# 14_Zynq_Power.net
KiCad netlist of a schematic drawn in Altium Designer
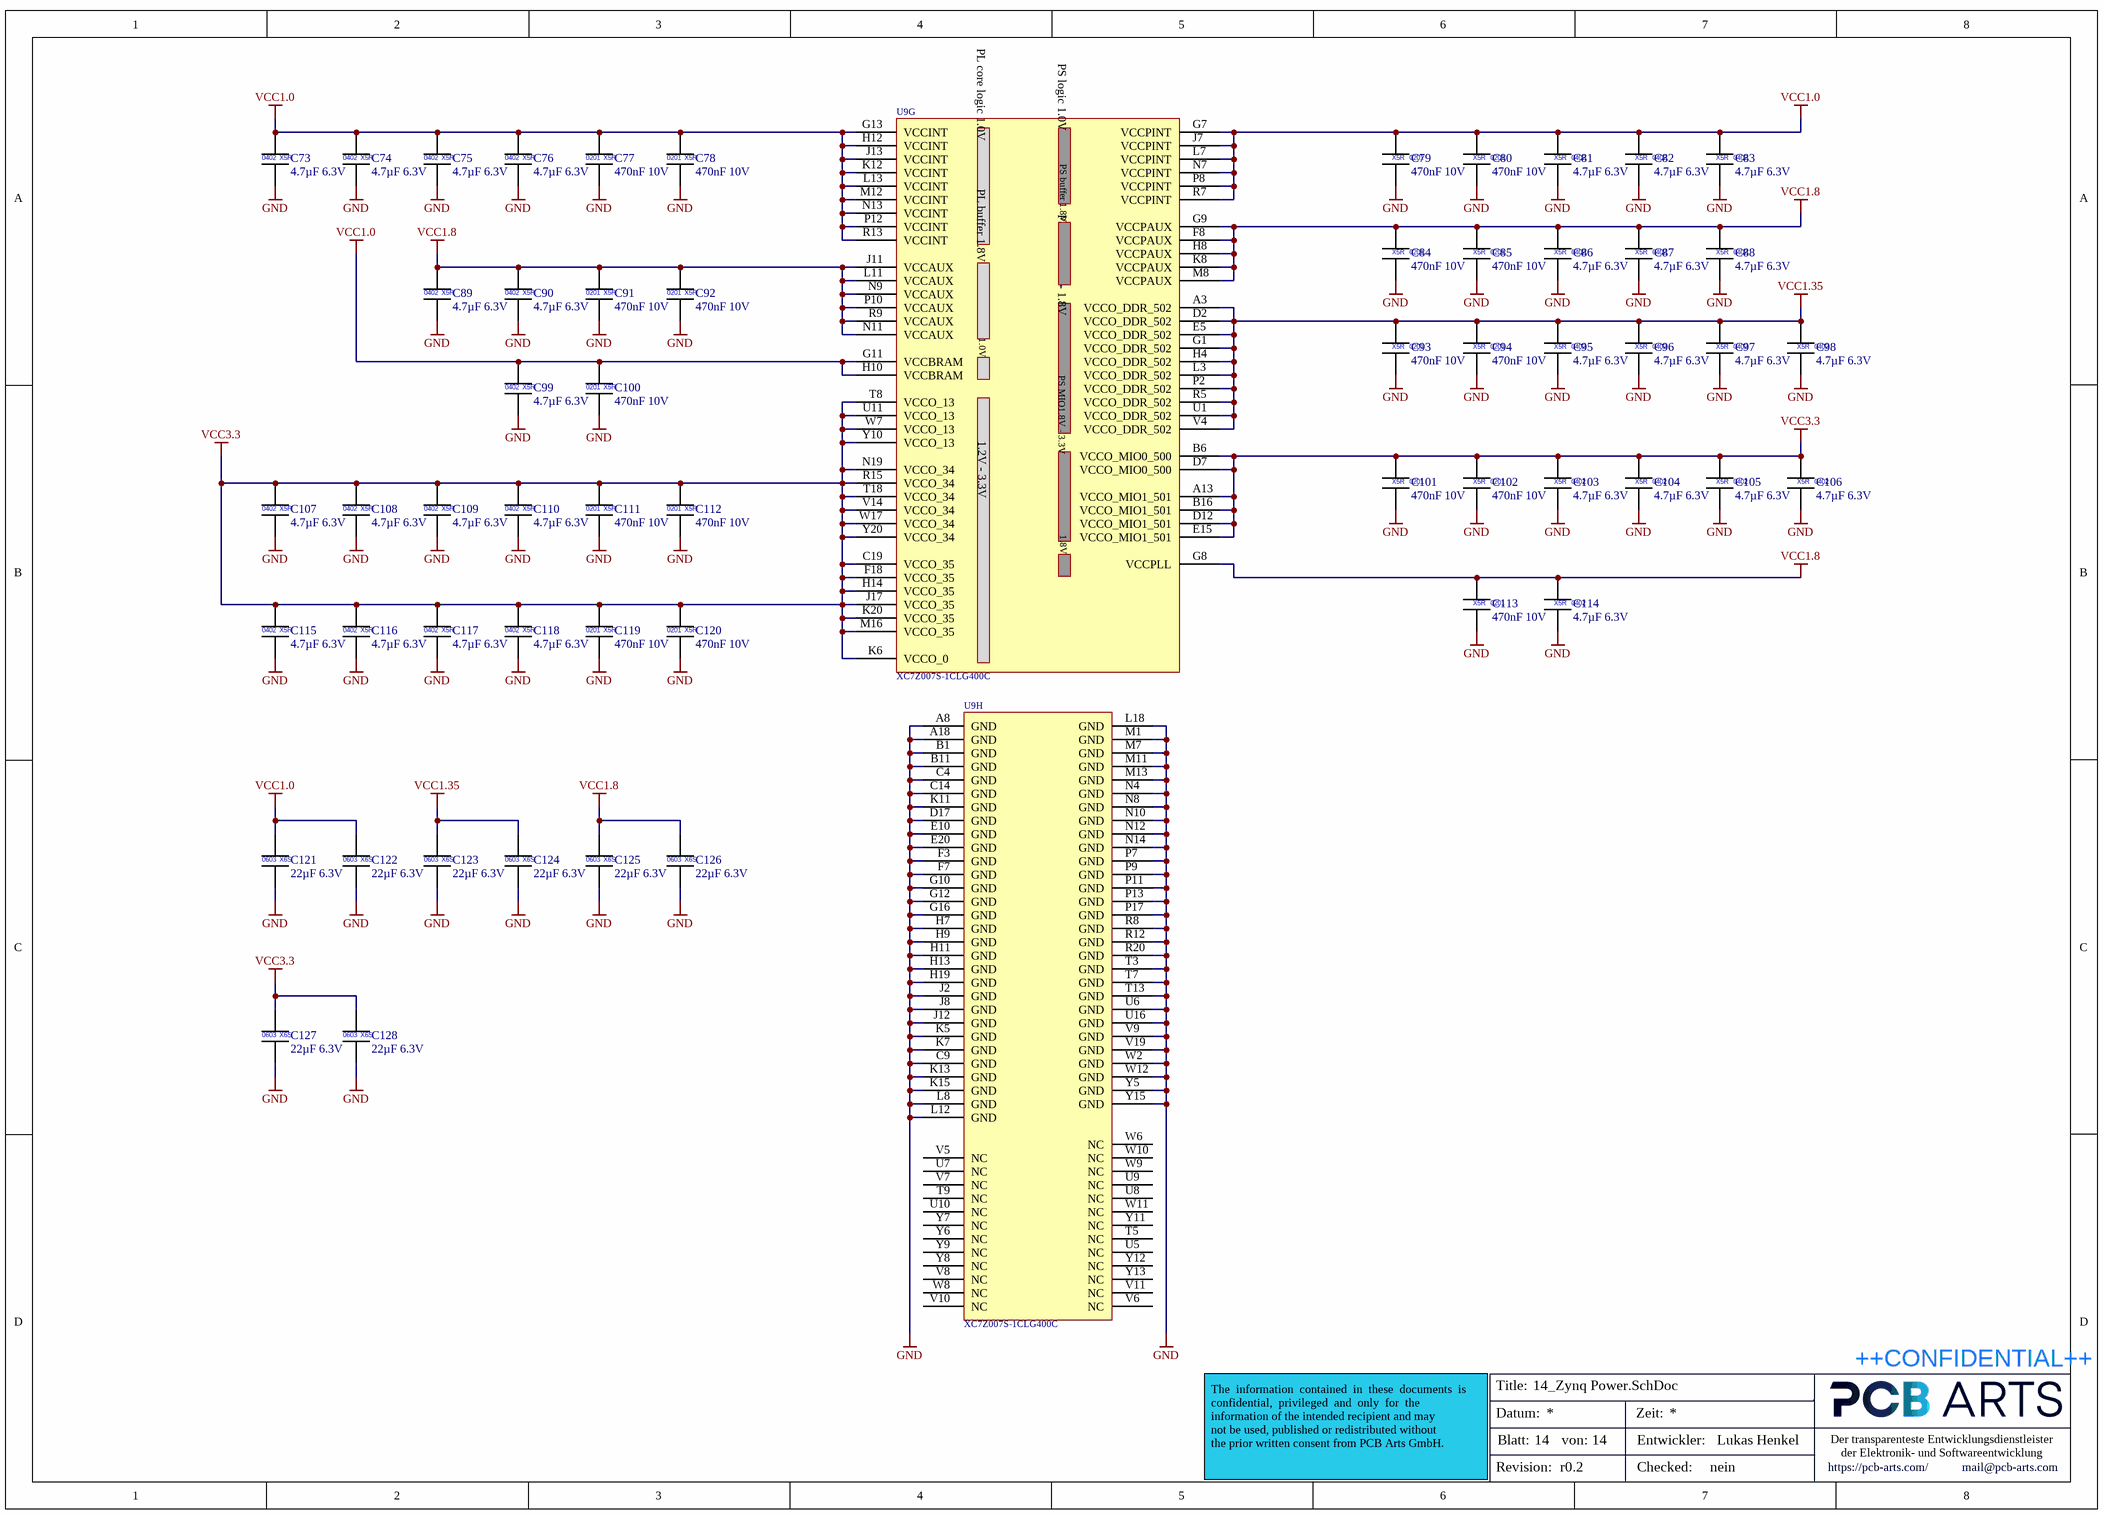
[diagram p0: 14_Zynq Power.SchDoc]

(export (version "E")
  (design (tool "Eeschema 10.0.6"))
  (components
    (comp (ref "C73")
      (value "4.7µF 6.3V")
      (footprint "Zynq-Feather-HD:CAPC1005X06L")
      (description "Multilayer Ceramic Capacitors MLCC - SMD/SMT 0402 6.3VDC")
      (libsource (lib "Zynq-Feather-HD") (part "CAP_0402_4.7µ_6.3V"))
    )
    (comp (ref "C74")
      (value "4.7µF 6.3V")
      (footprint "Zynq-Feather-HD:CAPC1005X06L")
      (description "Multilayer Ceramic Capacitors MLCC - SMD/SMT 0402 6.3VDC")
      (libsource (lib "Zynq-Feather-HD") (part "CAP_0402_4.7µ_6.3V"))
    )
    (comp (ref "C75")
      (value "4.7µF 6.3V")
      (footprint "Zynq-Feather-HD:CAPC1005X06L")
      (description "Multilayer Ceramic Capacitors MLCC - SMD/SMT 0402 6.3VDC")
      (libsource (lib "Zynq-Feather-HD") (part "CAP_0402_4.7µ_6.3V"))
    )
    (comp (ref "C76")
      (value "4.7µF 6.3V")
      (footprint "Zynq-Feather-HD:CAPC1005X06L")
      (description "Multilayer Ceramic Capacitors MLCC - SMD/SMT 0402 6.3VDC")
      (libsource (lib "Zynq-Feather-HD") (part "CAP_0402_4.7µ_6.3V"))
    )
    (comp (ref "C77")
      (value "470nF 10V")
      (footprint "Zynq-Feather-HD:CAPC0603X03L")
      (description "Multilayer Ceramic Capacitors MLCC - SMD/SMT 0201 10VDC")
      (libsource (lib "Zynq-Feather-HD") (part "CAP_0201_470nF_10V"))
    )
    (comp (ref "C78")
      (value "470nF 10V")
      (footprint "Zynq-Feather-HD:CAPC0603X03L")
      (description "Multilayer Ceramic Capacitors MLCC - SMD/SMT 0201 10VDC")
      (libsource (lib "Zynq-Feather-HD") (part "CAP_0201_470nF_10V"))
    )
    (comp (ref "C79")
      (value "470nF 10V")
      (footprint "Zynq-Feather-HD:CAPC0603X03L")
      (description "Multilayer Ceramic Capacitors MLCC - SMD/SMT 0201 10VDC")
      (libsource (lib "Zynq-Feather-HD") (part "CAP_0201_470nF_10V"))
    )
    (comp (ref "C80")
      (value "470nF 10V")
      (footprint "Zynq-Feather-HD:CAPC0603X03L")
      (description "Multilayer Ceramic Capacitors MLCC - SMD/SMT 0201 10VDC")
      (libsource (lib "Zynq-Feather-HD") (part "CAP_0201_470nF_10V"))
    )
    (comp (ref "C81")
      (value "4.7µF 6.3V")
      (footprint "Zynq-Feather-HD:CAPC1005X06L")
      (description "Multilayer Ceramic Capacitors MLCC - SMD/SMT 0402 6.3VDC")
      (libsource (lib "Zynq-Feather-HD") (part "CAP_0402_4.7µ_6.3V"))
    )
    (comp (ref "C82")
      (value "4.7µF 6.3V")
      (footprint "Zynq-Feather-HD:CAPC1005X06L")
      (description "Multilayer Ceramic Capacitors MLCC - SMD/SMT 0402 6.3VDC")
      (libsource (lib "Zynq-Feather-HD") (part "CAP_0402_4.7µ_6.3V"))
    )
    (comp (ref "C83")
      (value "4.7µF 6.3V")
      (footprint "Zynq-Feather-HD:CAPC1005X06L")
      (description "Multilayer Ceramic Capacitors MLCC - SMD/SMT 0402 6.3VDC")
      (libsource (lib "Zynq-Feather-HD") (part "CAP_0402_4.7µ_6.3V"))
    )
    (comp (ref "C84")
      (value "470nF 10V")
      (footprint "Zynq-Feather-HD:CAPC0603X03L")
      (description "Multilayer Ceramic Capacitors MLCC - SMD/SMT 0201 10VDC")
      (libsource (lib "Zynq-Feather-HD") (part "CAP_0201_470nF_10V"))
    )
    (comp (ref "C85")
      (value "470nF 10V")
      (footprint "Zynq-Feather-HD:CAPC0603X03L")
      (description "Multilayer Ceramic Capacitors MLCC - SMD/SMT 0201 10VDC")
      (libsource (lib "Zynq-Feather-HD") (part "CAP_0201_470nF_10V"))
    )
    (comp (ref "C86")
      (value "4.7µF 6.3V")
      (footprint "Zynq-Feather-HD:CAPC1005X06L")
      (description "Multilayer Ceramic Capacitors MLCC - SMD/SMT 0402 6.3VDC")
      (libsource (lib "Zynq-Feather-HD") (part "CAP_0402_4.7µ_6.3V"))
    )
    (comp (ref "C87")
      (value "4.7µF 6.3V")
      (footprint "Zynq-Feather-HD:CAPC1005X06L")
      (description "Multilayer Ceramic Capacitors MLCC - SMD/SMT 0402 6.3VDC")
      (libsource (lib "Zynq-Feather-HD") (part "CAP_0402_4.7µ_6.3V"))
    )
    (comp (ref "C88")
      (value "4.7µF 6.3V")
      (footprint "Zynq-Feather-HD:CAPC1005X06L")
      (description "Multilayer Ceramic Capacitors MLCC - SMD/SMT 0402 6.3VDC")
      (libsource (lib "Zynq-Feather-HD") (part "CAP_0402_4.7µ_6.3V"))
    )
    (comp (ref "C89")
      (value "4.7µF 6.3V")
      (footprint "Zynq-Feather-HD:CAPC1005X06L")
      (description "Multilayer Ceramic Capacitors MLCC - SMD/SMT 0402 6.3VDC")
      (libsource (lib "Zynq-Feather-HD") (part "CAP_0402_4.7µ_6.3V"))
    )
    (comp (ref "C90")
      (value "4.7µF 6.3V")
      (footprint "Zynq-Feather-HD:CAPC1005X06L")
      (description "Multilayer Ceramic Capacitors MLCC - SMD/SMT 0402 6.3VDC")
      (libsource (lib "Zynq-Feather-HD") (part "CAP_0402_4.7µ_6.3V"))
    )
    (comp (ref "C91")
      (value "470nF 10V")
      (footprint "Zynq-Feather-HD:CAPC0603X03L")
      (description "Multilayer Ceramic Capacitors MLCC - SMD/SMT 0201 10VDC")
      (libsource (lib "Zynq-Feather-HD") (part "CAP_0201_470nF_10V"))
    )
    (comp (ref "C92")
      (value "470nF 10V")
      (footprint "Zynq-Feather-HD:CAPC0603X03L")
      (description "Multilayer Ceramic Capacitors MLCC - SMD/SMT 0201 10VDC")
      (libsource (lib "Zynq-Feather-HD") (part "CAP_0201_470nF_10V"))
    )
    (comp (ref "C93")
      (value "470nF 10V")
      (footprint "Zynq-Feather-HD:CAPC0603X03L")
      (description "Multilayer Ceramic Capacitors MLCC - SMD/SMT 0201 10VDC")
      (libsource (lib "Zynq-Feather-HD") (part "CAP_0201_470nF_10V"))
    )
    (comp (ref "C94")
      (value "470nF 10V")
      (footprint "Zynq-Feather-HD:CAPC0603X03L")
      (description "Multilayer Ceramic Capacitors MLCC - SMD/SMT 0201 10VDC")
      (libsource (lib "Zynq-Feather-HD") (part "CAP_0201_470nF_10V"))
    )
    (comp (ref "C95")
      (value "4.7µF 6.3V")
      (footprint "Zynq-Feather-HD:CAPC1005X06L")
      (description "Multilayer Ceramic Capacitors MLCC - SMD/SMT 0402 6.3VDC")
      (libsource (lib "Zynq-Feather-HD") (part "CAP_0402_4.7µ_6.3V"))
    )
    (comp (ref "C96")
      (value "4.7µF 6.3V")
      (footprint "Zynq-Feather-HD:CAPC1005X06L")
      (description "Multilayer Ceramic Capacitors MLCC - SMD/SMT 0402 6.3VDC")
      (libsource (lib "Zynq-Feather-HD") (part "CAP_0402_4.7µ_6.3V"))
    )
    (comp (ref "C97")
      (value "4.7µF 6.3V")
      (footprint "Zynq-Feather-HD:CAPC1005X06L")
      (description "Multilayer Ceramic Capacitors MLCC - SMD/SMT 0402 6.3VDC")
      (libsource (lib "Zynq-Feather-HD") (part "CAP_0402_4.7µ_6.3V"))
    )
    (comp (ref "C98")
      (value "4.7µF 6.3V")
      (footprint "Zynq-Feather-HD:CAPC1005X06L")
      (description "Multilayer Ceramic Capacitors MLCC - SMD/SMT 0402 6.3VDC")
      (libsource (lib "Zynq-Feather-HD") (part "CAP_0402_4.7µ_6.3V"))
    )
    (comp (ref "C99")
      (value "4.7µF 6.3V")
      (footprint "Zynq-Feather-HD:CAPC1005X06L")
      (description "Multilayer Ceramic Capacitors MLCC - SMD/SMT 0402 6.3VDC")
      (libsource (lib "Zynq-Feather-HD") (part "CAP_0402_4.7µ_6.3V"))
    )
    (comp (ref "C100")
      (value "470nF 10V")
      (footprint "Zynq-Feather-HD:CAPC0603X03L")
      (description "Multilayer Ceramic Capacitors MLCC - SMD/SMT 0201 10VDC")
      (libsource (lib "Zynq-Feather-HD") (part "CAP_0201_470nF_10V"))
    )
    (comp (ref "C101")
      (value "470nF 10V")
      (footprint "Zynq-Feather-HD:CAPC0603X03L")
      (description "Multilayer Ceramic Capacitors MLCC - SMD/SMT 0201 10VDC")
      (libsource (lib "Zynq-Feather-HD") (part "CAP_0201_470nF_10V"))
    )
    (comp (ref "C102")
      (value "470nF 10V")
      (footprint "Zynq-Feather-HD:CAPC0603X03L")
      (description "Multilayer Ceramic Capacitors MLCC - SMD/SMT 0201 10VDC")
      (libsource (lib "Zynq-Feather-HD") (part "CAP_0201_470nF_10V"))
    )
    (comp (ref "C103")
      (value "4.7µF 6.3V")
      (footprint "Zynq-Feather-HD:CAPC1005X06L")
      (description "Multilayer Ceramic Capacitors MLCC - SMD/SMT 0402 6.3VDC")
      (libsource (lib "Zynq-Feather-HD") (part "CAP_0402_4.7µ_6.3V"))
    )
    (comp (ref "C104")
      (value "4.7µF 6.3V")
      (footprint "Zynq-Feather-HD:CAPC1005X06L")
      (description "Multilayer Ceramic Capacitors MLCC - SMD/SMT 0402 6.3VDC")
      (libsource (lib "Zynq-Feather-HD") (part "CAP_0402_4.7µ_6.3V"))
    )
    (comp (ref "C105")
      (value "4.7µF 6.3V")
      (footprint "Zynq-Feather-HD:CAPC1005X06L")
      (description "Multilayer Ceramic Capacitors MLCC - SMD/SMT 0402 6.3VDC")
      (libsource (lib "Zynq-Feather-HD") (part "CAP_0402_4.7µ_6.3V"))
    )
    (comp (ref "C106")
      (value "4.7µF 6.3V")
      (footprint "Zynq-Feather-HD:CAPC1005X06L")
      (description "Multilayer Ceramic Capacitors MLCC - SMD/SMT 0402 6.3VDC")
      (libsource (lib "Zynq-Feather-HD") (part "CAP_0402_4.7µ_6.3V"))
    )
    (comp (ref "C107")
      (value "4.7µF 6.3V")
      (footprint "Zynq-Feather-HD:CAPC1005X06L")
      (description "Multilayer Ceramic Capacitors MLCC - SMD/SMT 0402 6.3VDC")
      (libsource (lib "Zynq-Feather-HD") (part "CAP_0402_4.7µ_6.3V"))
    )
    (comp (ref "C108")
      (value "4.7µF 6.3V")
      (footprint "Zynq-Feather-HD:CAPC1005X06L")
      (description "Multilayer Ceramic Capacitors MLCC - SMD/SMT 0402 6.3VDC")
      (libsource (lib "Zynq-Feather-HD") (part "CAP_0402_4.7µ_6.3V"))
    )
    (comp (ref "C109")
      (value "4.7µF 6.3V")
      (footprint "Zynq-Feather-HD:CAPC1005X06L")
      (description "Multilayer Ceramic Capacitors MLCC - SMD/SMT 0402 6.3VDC")
      (libsource (lib "Zynq-Feather-HD") (part "CAP_0402_4.7µ_6.3V"))
    )
    (comp (ref "C110")
      (value "4.7µF 6.3V")
      (footprint "Zynq-Feather-HD:CAPC1005X06L")
      (description "Multilayer Ceramic Capacitors MLCC - SMD/SMT 0402 6.3VDC")
      (libsource (lib "Zynq-Feather-HD") (part "CAP_0402_4.7µ_6.3V"))
    )
    (comp (ref "C111")
      (value "470nF 10V")
      (footprint "Zynq-Feather-HD:CAPC0603X03L")
      (description "Multilayer Ceramic Capacitors MLCC - SMD/SMT 0201 10VDC")
      (libsource (lib "Zynq-Feather-HD") (part "CAP_0201_470nF_10V"))
    )
    (comp (ref "C112")
      (value "470nF 10V")
      (footprint "Zynq-Feather-HD:CAPC0603X03L")
      (description "Multilayer Ceramic Capacitors MLCC - SMD/SMT 0201 10VDC")
      (libsource (lib "Zynq-Feather-HD") (part "CAP_0201_470nF_10V"))
    )
    (comp (ref "C113")
      (value "470nF 10V")
      (footprint "Zynq-Feather-HD:CAPC0603X03L")
      (description "Multilayer Ceramic Capacitors MLCC - SMD/SMT 0201 10VDC")
      (libsource (lib "Zynq-Feather-HD") (part "CAP_0201_470nF_10V"))
    )
    (comp (ref "C114")
      (value "4.7µF 6.3V")
      (footprint "Zynq-Feather-HD:CAPC1005X06L")
      (description "Multilayer Ceramic Capacitors MLCC - SMD/SMT 0402 6.3VDC")
      (libsource (lib "Zynq-Feather-HD") (part "CAP_0402_4.7µ_6.3V"))
    )
    (comp (ref "C115")
      (value "4.7µF 6.3V")
      (footprint "Zynq-Feather-HD:CAPC1005X06L")
      (description "Multilayer Ceramic Capacitors MLCC - SMD/SMT 0402 6.3VDC")
      (libsource (lib "Zynq-Feather-HD") (part "CAP_0402_4.7µ_6.3V"))
    )
    (comp (ref "C116")
      (value "4.7µF 6.3V")
      (footprint "Zynq-Feather-HD:CAPC1005X06L")
      (description "Multilayer Ceramic Capacitors MLCC - SMD/SMT 0402 6.3VDC")
      (libsource (lib "Zynq-Feather-HD") (part "CAP_0402_4.7µ_6.3V"))
    )
    (comp (ref "C117")
      (value "4.7µF 6.3V")
      (footprint "Zynq-Feather-HD:CAPC1005X06L")
      (description "Multilayer Ceramic Capacitors MLCC - SMD/SMT 0402 6.3VDC")
      (libsource (lib "Zynq-Feather-HD") (part "CAP_0402_4.7µ_6.3V"))
    )
    (comp (ref "C118")
      (value "4.7µF 6.3V")
      (footprint "Zynq-Feather-HD:CAPC1005X06L")
      (description "Multilayer Ceramic Capacitors MLCC - SMD/SMT 0402 6.3VDC")
      (libsource (lib "Zynq-Feather-HD") (part "CAP_0402_4.7µ_6.3V"))
    )
    (comp (ref "C119")
      (value "470nF 10V")
      (footprint "Zynq-Feather-HD:CAPC0603X03L")
      (description "Multilayer Ceramic Capacitors MLCC - SMD/SMT 0201 10VDC")
      (libsource (lib "Zynq-Feather-HD") (part "CAP_0201_470nF_10V"))
    )
    (comp (ref "C120")
      (value "470nF 10V")
      (footprint "Zynq-Feather-HD:CAPC0603X03L")
      (description "Multilayer Ceramic Capacitors MLCC - SMD/SMT 0201 10VDC")
      (libsource (lib "Zynq-Feather-HD") (part "CAP_0201_470nF_10V"))
    )
    (comp (ref "C121")
      (value "22µF 6.3V")
      (footprint "Zynq-Feather-HD:CAPC1608X10L")
      (description "Multilayer Ceramic Capacitors MLCC - SMD/SMT 0603 6.3VDC")
      (libsource (lib "Zynq-Feather-HD") (part "CAP_0603_22µ_6.3V"))
    )
    (comp (ref "C122")
      (value "22µF 6.3V")
      (footprint "Zynq-Feather-HD:CAPC1608X10L")
      (description "Multilayer Ceramic Capacitors MLCC - SMD/SMT 0603 6.3VDC")
      (libsource (lib "Zynq-Feather-HD") (part "CAP_0603_22µ_6.3V"))
    )
    (comp (ref "C123")
      (value "22µF 6.3V")
      (footprint "Zynq-Feather-HD:CAPC1608X10L")
      (description "Multilayer Ceramic Capacitors MLCC - SMD/SMT 0603 6.3VDC")
      (libsource (lib "Zynq-Feather-HD") (part "CAP_0603_22µ_6.3V"))
    )
    (comp (ref "C124")
      (value "22µF 6.3V")
      (footprint "Zynq-Feather-HD:CAPC1608X10L")
      (description "Multilayer Ceramic Capacitors MLCC - SMD/SMT 0603 6.3VDC")
      (libsource (lib "Zynq-Feather-HD") (part "CAP_0603_22µ_6.3V"))
    )
    (comp (ref "C125")
      (value "22µF 6.3V")
      (footprint "Zynq-Feather-HD:CAPC1608X10L")
      (description "Multilayer Ceramic Capacitors MLCC - SMD/SMT 0603 6.3VDC")
      (libsource (lib "Zynq-Feather-HD") (part "CAP_0603_22µ_6.3V"))
    )
    (comp (ref "C126")
      (value "22µF 6.3V")
      (footprint "Zynq-Feather-HD:CAPC1608X10L")
      (description "Multilayer Ceramic Capacitors MLCC - SMD/SMT 0603 6.3VDC")
      (libsource (lib "Zynq-Feather-HD") (part "CAP_0603_22µ_6.3V"))
    )
    (comp (ref "C127")
      (value "22µF 6.3V")
      (footprint "Zynq-Feather-HD:CAPC1608X10L")
      (description "Multilayer Ceramic Capacitors MLCC - SMD/SMT 0603 6.3VDC")
      (libsource (lib "Zynq-Feather-HD") (part "CAP_0603_22µ_6.3V"))
    )
    (comp (ref "C128")
      (value "22µF 6.3V")
      (footprint "Zynq-Feather-HD:CAPC1608X10L")
      (description "Multilayer Ceramic Capacitors MLCC - SMD/SMT 0603 6.3VDC")
      (libsource (lib "Zynq-Feather-HD") (part "CAP_0603_22µ_6.3V"))
    )
    (comp (ref "U9")
      (value "XC7Z007S-1CLG400C")
      (footprint "Zynq-Feather-HD:BGA400C80P20X20_1700X1700X160")
      (description "XC7Z007S-1CLG400C_Processors - Application Specialised")
      (libsource (lib "Zynq-Feather-HD") (part "XC7Z007S-1CLG400C_Processors - Application Specialised"))
    )
  )
  (nets
    (net (code "1") (name "GND") (class "Default")
      (node (ref "C100") (pin "2") (pinfunction "2_2") (pintype "passive"))
      (node (ref "C101") (pin "2") (pinfunction "2_2") (pintype "passive"))
      (node (ref "C102") (pin "2") (pinfunction "2_2") (pintype "passive"))
      (node (ref "C103") (pin "2") (pinfunction "2_2") (pintype "passive"))
      (node (ref "C104") (pin "2") (pinfunction "2_2") (pintype "passive"))
      (node (ref "C105") (pin "2") (pinfunction "2_2") (pintype "passive"))
      (node (ref "C106") (pin "2") (pinfunction "2_2") (pintype "passive"))
      (node (ref "C107") (pin "2") (pinfunction "2_2") (pintype "passive"))
      (node (ref "C108") (pin "2") (pinfunction "2_2") (pintype "passive"))
      (node (ref "C109") (pin "2") (pinfunction "2_2") (pintype "passive"))
      (node (ref "C110") (pin "2") (pinfunction "2_2") (pintype "passive"))
      (node (ref "C111") (pin "2") (pinfunction "2_2") (pintype "passive"))
      (node (ref "C112") (pin "2") (pinfunction "2_2") (pintype "passive"))
      (node (ref "C113") (pin "2") (pinfunction "2_2") (pintype "passive"))
      (node (ref "C114") (pin "2") (pinfunction "2_2") (pintype "passive"))
      (node (ref "C115") (pin "2") (pinfunction "2_2") (pintype "passive"))
      (node (ref "C116") (pin "2") (pinfunction "2_2") (pintype "passive"))
      (node (ref "C117") (pin "2") (pinfunction "2_2") (pintype "passive"))
      (node (ref "C118") (pin "2") (pinfunction "2_2") (pintype "passive"))
      (node (ref "C119") (pin "2") (pinfunction "2_2") (pintype "passive"))
      (node (ref "C120") (pin "2") (pinfunction "2_2") (pintype "passive"))
      (node (ref "C121") (pin "2") (pinfunction "2_2") (pintype "passive"))
      (node (ref "C122") (pin "2") (pinfunction "2_2") (pintype "passive"))
      (node (ref "C123") (pin "2") (pinfunction "2_2") (pintype "passive"))
      (node (ref "C124") (pin "2") (pinfunction "2_2") (pintype "passive"))
      (node (ref "C125") (pin "2") (pinfunction "2_2") (pintype "passive"))
      (node (ref "C126") (pin "2") (pinfunction "2_2") (pintype "passive"))
      (node (ref "C127") (pin "2") (pinfunction "2_2") (pintype "passive"))
      (node (ref "C128") (pin "2") (pinfunction "2_2") (pintype "passive"))
      (node (ref "C73") (pin "2") (pinfunction "2_2") (pintype "passive"))
      (node (ref "C74") (pin "2") (pinfunction "2_2") (pintype "passive"))
      (node (ref "C75") (pin "2") (pinfunction "2_2") (pintype "passive"))
      (node (ref "C76") (pin "2") (pinfunction "2_2") (pintype "passive"))
      (node (ref "C77") (pin "2") (pinfunction "2_2") (pintype "passive"))
      (node (ref "C78") (pin "2") (pinfunction "2_2") (pintype "passive"))
      (node (ref "C79") (pin "2") (pinfunction "2_2") (pintype "passive"))
      (node (ref "C80") (pin "2") (pinfunction "2_2") (pintype "passive"))
      (node (ref "C81") (pin "2") (pinfunction "2_2") (pintype "passive"))
      (node (ref "C82") (pin "2") (pinfunction "2_2") (pintype "passive"))
      (node (ref "C83") (pin "2") (pinfunction "2_2") (pintype "passive"))
      (node (ref "C84") (pin "2") (pinfunction "2_2") (pintype "passive"))
      (node (ref "C85") (pin "2") (pinfunction "2_2") (pintype "passive"))
      (node (ref "C86") (pin "2") (pinfunction "2_2") (pintype "passive"))
      (node (ref "C87") (pin "2") (pinfunction "2_2") (pintype "passive"))
      (node (ref "C88") (pin "2") (pinfunction "2_2") (pintype "passive"))
      (node (ref "C89") (pin "2") (pinfunction "2_2") (pintype "passive"))
      (node (ref "C90") (pin "2") (pinfunction "2_2") (pintype "passive"))
      (node (ref "C91") (pin "2") (pinfunction "2_2") (pintype "passive"))
      (node (ref "C92") (pin "2") (pinfunction "2_2") (pintype "passive"))
      (node (ref "C93") (pin "2") (pinfunction "2_2") (pintype "passive"))
      (node (ref "C94") (pin "2") (pinfunction "2_2") (pintype "passive"))
      (node (ref "C95") (pin "2") (pinfunction "2_2") (pintype "passive"))
      (node (ref "C96") (pin "2") (pinfunction "2_2") (pintype "passive"))
      (node (ref "C97") (pin "2") (pinfunction "2_2") (pintype "passive"))
      (node (ref "C98") (pin "2") (pinfunction "2_2") (pintype "passive"))
      (node (ref "C99") (pin "2") (pinfunction "2_2") (pintype "passive"))
      (node (ref "U9") (pin "A18") (pinfunction "GND_A18") (pintype "passive"))
      (node (ref "U9") (pin "A8") (pinfunction "GND_A8") (pintype "passive"))
      (node (ref "U9") (pin "B1") (pinfunction "GND_B1") (pintype "passive"))
      (node (ref "U9") (pin "B11") (pinfunction "GND_B11") (pintype "passive"))
      (node (ref "U9") (pin "C14") (pinfunction "GND_C14") (pintype "passive"))
      (node (ref "U9") (pin "C4") (pinfunction "GND_C4") (pintype "passive"))
      (node (ref "U9") (pin "C9") (pinfunction "GND_C9") (pintype "passive"))
      (node (ref "U9") (pin "D17") (pinfunction "GND_D17") (pintype "passive"))
      (node (ref "U9") (pin "E10") (pinfunction "GND_E10") (pintype "passive"))
      (node (ref "U9") (pin "E20") (pinfunction "GND_E20") (pintype "passive"))
      (node (ref "U9") (pin "F3") (pinfunction "GND_F3") (pintype "passive"))
      (node (ref "U9") (pin "F7") (pinfunction "GND_F7") (pintype "passive"))
      (node (ref "U9") (pin "G10") (pinfunction "GND_G10") (pintype "passive"))
      (node (ref "U9") (pin "G12") (pinfunction "GND_G12") (pintype "passive"))
      (node (ref "U9") (pin "G16") (pinfunction "GND_G16") (pintype "passive"))
      (node (ref "U9") (pin "H11") (pinfunction "GND_H11") (pintype "passive"))
      (node (ref "U9") (pin "H13") (pinfunction "GND_H13") (pintype "passive"))
      (node (ref "U9") (pin "H19") (pinfunction "GND_H19") (pintype "passive"))
      (node (ref "U9") (pin "H7") (pinfunction "GND_H7") (pintype "passive"))
      (node (ref "U9") (pin "H9") (pinfunction "GND_H9") (pintype "passive"))
      (node (ref "U9") (pin "J12") (pinfunction "GND_J12") (pintype "passive"))
      (node (ref "U9") (pin "J2") (pinfunction "GND_J2") (pintype "passive"))
      (node (ref "U9") (pin "J8") (pinfunction "GND_J8") (pintype "passive"))
      (node (ref "U9") (pin "K11") (pinfunction "GND_K11") (pintype "passive"))
      (node (ref "U9") (pin "K13") (pinfunction "GND_K13") (pintype "passive"))
      (node (ref "U9") (pin "K15") (pinfunction "GND_K15") (pintype "passive"))
      (node (ref "U9") (pin "K5") (pinfunction "GND_K5") (pintype "passive"))
      (node (ref "U9") (pin "K7") (pinfunction "GND_K7") (pintype "passive"))
      (node (ref "U9") (pin "L12") (pinfunction "GND_L12") (pintype "passive"))
      (node (ref "U9") (pin "L18") (pinfunction "GND_L18") (pintype "passive"))
      (node (ref "U9") (pin "L8") (pinfunction "GND_L8") (pintype "passive"))
      (node (ref "U9") (pin "M1") (pinfunction "GND_M1") (pintype "passive"))
      (node (ref "U9") (pin "M11") (pinfunction "GND_M11") (pintype "passive"))
      (node (ref "U9") (pin "M13") (pinfunction "GND_M13") (pintype "passive"))
      (node (ref "U9") (pin "M7") (pinfunction "GND_M7") (pintype "passive"))
      (node (ref "U9") (pin "N10") (pinfunction "GND_N10") (pintype "passive"))
      (node (ref "U9") (pin "N12") (pinfunction "GND_N12") (pintype "passive"))
      (node (ref "U9") (pin "N14") (pinfunction "GND_N14") (pintype "passive"))
      (node (ref "U9") (pin "N4") (pinfunction "GND_N4") (pintype "passive"))
      (node (ref "U9") (pin "N8") (pinfunction "GND_N8") (pintype "passive"))
      (node (ref "U9") (pin "P11") (pinfunction "GND_P11") (pintype "passive"))
      (node (ref "U9") (pin "P13") (pinfunction "GND_P13") (pintype "passive"))
      (node (ref "U9") (pin "P17") (pinfunction "GND_P17") (pintype "passive"))
      (node (ref "U9") (pin "P7") (pinfunction "GND_P7") (pintype "passive"))
      (node (ref "U9") (pin "P9") (pinfunction "GND_P9") (pintype "passive"))
      (node (ref "U9") (pin "R12") (pinfunction "GND_R12") (pintype "passive"))
      (node (ref "U9") (pin "R20") (pinfunction "GND_R20") (pintype "passive"))
      (node (ref "U9") (pin "R8") (pinfunction "GND_R8") (pintype "passive"))
      (node (ref "U9") (pin "T13") (pinfunction "GND_T13") (pintype "passive"))
      (node (ref "U9") (pin "T3") (pinfunction "GND_T3") (pintype "passive"))
      (node (ref "U9") (pin "T7") (pinfunction "GND_T7") (pintype "passive"))
      (node (ref "U9") (pin "U16") (pinfunction "GND_U16") (pintype "passive"))
      (node (ref "U9") (pin "U6") (pinfunction "GND_U6") (pintype "passive"))
      (node (ref "U9") (pin "V19") (pinfunction "GND_V19") (pintype "passive"))
      (node (ref "U9") (pin "V9") (pinfunction "GND_V9") (pintype "passive"))
      (node (ref "U9") (pin "W12") (pinfunction "GND_W12") (pintype "passive"))
      (node (ref "U9") (pin "W2") (pinfunction "GND_W2") (pintype "passive"))
      (node (ref "U9") (pin "Y15") (pinfunction "GND_Y15") (pintype "passive"))
      (node (ref "U9") (pin "Y5") (pinfunction "GND_Y5") (pintype "passive"))
    )
    (net (code "2") (name "VCC1.0") (class "Default")
      (node (ref "C100") (pin "1") (pinfunction "1_1") (pintype "passive"))
      (node (ref "C121") (pin "1") (pinfunction "1_1") (pintype "passive"))
      (node (ref "C122") (pin "1") (pinfunction "1_1") (pintype "passive"))
      (node (ref "C73") (pin "1") (pinfunction "1_1") (pintype "passive"))
      (node (ref "C74") (pin "1") (pinfunction "1_1") (pintype "passive"))
      (node (ref "C75") (pin "1") (pinfunction "1_1") (pintype "passive"))
      (node (ref "C76") (pin "1") (pinfunction "1_1") (pintype "passive"))
      (node (ref "C77") (pin "1") (pinfunction "1_1") (pintype "passive"))
      (node (ref "C78") (pin "1") (pinfunction "1_1") (pintype "passive"))
      (node (ref "C79") (pin "1") (pinfunction "1_1") (pintype "passive"))
      (node (ref "C80") (pin "1") (pinfunction "1_1") (pintype "passive"))
      (node (ref "C81") (pin "1") (pinfunction "1_1") (pintype "passive"))
      (node (ref "C82") (pin "1") (pinfunction "1_1") (pintype "passive"))
      (node (ref "C83") (pin "1") (pinfunction "1_1") (pintype "passive"))
      (node (ref "C99") (pin "1") (pinfunction "1_1") (pintype "passive"))
      (node (ref "U9") (pin "G11") (pinfunction "VCCBRAM_G11") (pintype "passive"))
      (node (ref "U9") (pin "G13") (pinfunction "VCCINT_G13") (pintype "passive"))
      (node (ref "U9") (pin "G7") (pinfunction "VCCPINT_G7") (pintype "passive"))
      (node (ref "U9") (pin "H10") (pinfunction "VCCBRAM_H10") (pintype "passive"))
      (node (ref "U9") (pin "H12") (pinfunction "VCCINT_H12") (pintype "passive"))
      (node (ref "U9") (pin "J13") (pinfunction "VCCINT_J13") (pintype "passive"))
      (node (ref "U9") (pin "J7") (pinfunction "VCCPINT_J7") (pintype "passive"))
      (node (ref "U9") (pin "K12") (pinfunction "VCCINT_K12") (pintype "passive"))
      (node (ref "U9") (pin "L13") (pinfunction "VCCINT_L13") (pintype "passive"))
      (node (ref "U9") (pin "L7") (pinfunction "VCCPINT_L7") (pintype "passive"))
      (node (ref "U9") (pin "M12") (pinfunction "VCCINT_M12") (pintype "passive"))
      (node (ref "U9") (pin "N13") (pinfunction "VCCINT_N13") (pintype "passive"))
      (node (ref "U9") (pin "N7") (pinfunction "VCCPINT_N7") (pintype "passive"))
      (node (ref "U9") (pin "P12") (pinfunction "VCCINT_P12") (pintype "passive"))
      (node (ref "U9") (pin "P8") (pinfunction "VCCPINT_P8") (pintype "passive"))
      (node (ref "U9") (pin "R13") (pinfunction "VCCINT_R13") (pintype "passive"))
      (node (ref "U9") (pin "R7") (pinfunction "VCCPINT_R7") (pintype "passive"))
    )
    (net (code "3") (name "VCC1.8") (class "Default")
      (node (ref "C113") (pin "1") (pinfunction "1_1") (pintype "passive"))
      (node (ref "C114") (pin "1") (pinfunction "1_1") (pintype "passive"))
      (node (ref "C125") (pin "1") (pinfunction "1_1") (pintype "passive"))
      (node (ref "C126") (pin "1") (pinfunction "1_1") (pintype "passive"))
      (node (ref "C84") (pin "1") (pinfunction "1_1") (pintype "passive"))
      (node (ref "C85") (pin "1") (pinfunction "1_1") (pintype "passive"))
      (node (ref "C86") (pin "1") (pinfunction "1_1") (pintype "passive"))
      (node (ref "C87") (pin "1") (pinfunction "1_1") (pintype "passive"))
      (node (ref "C88") (pin "1") (pinfunction "1_1") (pintype "passive"))
      (node (ref "C89") (pin "1") (pinfunction "1_1") (pintype "passive"))
      (node (ref "C90") (pin "1") (pinfunction "1_1") (pintype "passive"))
      (node (ref "C91") (pin "1") (pinfunction "1_1") (pintype "passive"))
      (node (ref "C92") (pin "1") (pinfunction "1_1") (pintype "passive"))
      (node (ref "U9") (pin "F8") (pinfunction "VCCPAUX_F8") (pintype "passive"))
      (node (ref "U9") (pin "G8") (pinfunction "VCCPLL_G8") (pintype "passive"))
      (node (ref "U9") (pin "G9") (pinfunction "VCCPAUX_G9") (pintype "passive"))
      (node (ref "U9") (pin "H8") (pinfunction "VCCPAUX_H8") (pintype "passive"))
      (node (ref "U9") (pin "J11") (pinfunction "VCCAUX_J11") (pintype "passive"))
      (node (ref "U9") (pin "K8") (pinfunction "VCCPAUX_K8") (pintype "passive"))
      (node (ref "U9") (pin "L11") (pinfunction "VCCAUX_L11") (pintype "passive"))
      (node (ref "U9") (pin "M8") (pinfunction "VCCPAUX_M8") (pintype "passive"))
      (node (ref "U9") (pin "N11") (pinfunction "VCCAUX_N11") (pintype "passive"))
      (node (ref "U9") (pin "N9") (pinfunction "VCCAUX_N9") (pintype "passive"))
      (node (ref "U9") (pin "P10") (pinfunction "VCCAUX_P10") (pintype "passive"))
      (node (ref "U9") (pin "R9") (pinfunction "VCCAUX_R9") (pintype "passive"))
    )
    (net (code "4") (name "VCC1.35") (class "Default")
      (node (ref "C123") (pin "1") (pinfunction "1_1") (pintype "passive"))
      (node (ref "C124") (pin "1") (pinfunction "1_1") (pintype "passive"))
      (node (ref "C93") (pin "1") (pinfunction "1_1") (pintype "passive"))
      (node (ref "C94") (pin "1") (pinfunction "1_1") (pintype "passive"))
      (node (ref "C95") (pin "1") (pinfunction "1_1") (pintype "passive"))
      (node (ref "C96") (pin "1") (pinfunction "1_1") (pintype "passive"))
      (node (ref "C97") (pin "1") (pinfunction "1_1") (pintype "passive"))
      (node (ref "C98") (pin "1") (pinfunction "1_1") (pintype "passive"))
      (node (ref "U9") (pin "A3") (pinfunction "VCCO_DDR_502_A3") (pintype "passive"))
      (node (ref "U9") (pin "D2") (pinfunction "VCCO_DDR_502_D2") (pintype "passive"))
      (node (ref "U9") (pin "E5") (pinfunction "VCCO_DDR_502_E5") (pintype "passive"))
      (node (ref "U9") (pin "G1") (pinfunction "VCCO_DDR_502_G1") (pintype "passive"))
      (node (ref "U9") (pin "H4") (pinfunction "VCCO_DDR_502_H4") (pintype "passive"))
      (node (ref "U9") (pin "L3") (pinfunction "VCCO_DDR_502_L3") (pintype "passive"))
      (node (ref "U9") (pin "P2") (pinfunction "VCCO_DDR_502_P2") (pintype "passive"))
      (node (ref "U9") (pin "R5") (pinfunction "VCCO_DDR_502_R5") (pintype "passive"))
      (node (ref "U9") (pin "U1") (pinfunction "VCCO_DDR_502_U1") (pintype "passive"))
      (node (ref "U9") (pin "V4") (pinfunction "VCCO_DDR_502_V4") (pintype "passive"))
    )
    (net (code "5") (name "VCC3.3") (class "Default")
      (node (ref "C101") (pin "1") (pinfunction "1_1") (pintype "passive"))
      (node (ref "C102") (pin "1") (pinfunction "1_1") (pintype "passive"))
      (node (ref "C103") (pin "1") (pinfunction "1_1") (pintype "passive"))
      (node (ref "C104") (pin "1") (pinfunction "1_1") (pintype "passive"))
      (node (ref "C105") (pin "1") (pinfunction "1_1") (pintype "passive"))
      (node (ref "C106") (pin "1") (pinfunction "1_1") (pintype "passive"))
      (node (ref "C107") (pin "1") (pinfunction "1_1") (pintype "passive"))
      (node (ref "C108") (pin "1") (pinfunction "1_1") (pintype "passive"))
      (node (ref "C109") (pin "1") (pinfunction "1_1") (pintype "passive"))
      (node (ref "C110") (pin "1") (pinfunction "1_1") (pintype "passive"))
      (node (ref "C111") (pin "1") (pinfunction "1_1") (pintype "passive"))
      (node (ref "C112") (pin "1") (pinfunction "1_1") (pintype "passive"))
      (node (ref "C115") (pin "1") (pinfunction "1_1") (pintype "passive"))
      (node (ref "C116") (pin "1") (pinfunction "1_1") (pintype "passive"))
      (node (ref "C117") (pin "1") (pinfunction "1_1") (pintype "passive"))
      (node (ref "C118") (pin "1") (pinfunction "1_1") (pintype "passive"))
      (node (ref "C119") (pin "1") (pinfunction "1_1") (pintype "passive"))
      (node (ref "C120") (pin "1") (pinfunction "1_1") (pintype "passive"))
      (node (ref "C127") (pin "1") (pinfunction "1_1") (pintype "passive"))
      (node (ref "C128") (pin "1") (pinfunction "1_1") (pintype "passive"))
      (node (ref "U9") (pin "A13") (pinfunction "VCCO_MIO1_501_A13") (pintype "passive"))
      (node (ref "U9") (pin "B16") (pinfunction "VCCO_MIO1_501_B16") (pintype "passive"))
      (node (ref "U9") (pin "B6") (pinfunction "VCCO_MIO0_500_B6") (pintype "passive"))
      (node (ref "U9") (pin "C19") (pinfunction "VCCO_35_C19") (pintype "passive"))
      (node (ref "U9") (pin "D12") (pinfunction "VCCO_MIO1_501_D12") (pintype "passive"))
      (node (ref "U9") (pin "D7") (pinfunction "VCCO_MIO0_500_D7") (pintype "passive"))
      (node (ref "U9") (pin "E15") (pinfunction "VCCO_MIO1_501_E15") (pintype "passive"))
      (node (ref "U9") (pin "F18") (pinfunction "VCCO_35_F18") (pintype "passive"))
      (node (ref "U9") (pin "H14") (pinfunction "VCCO_35_H14") (pintype "passive"))
      (node (ref "U9") (pin "J17") (pinfunction "VCCO_35_J17") (pintype "passive"))
      (node (ref "U9") (pin "K20") (pinfunction "VCCO_35_K20") (pintype "passive"))
      (node (ref "U9") (pin "K6") (pinfunction "VCCO_0_K6") (pintype "passive"))
      (node (ref "U9") (pin "M16") (pinfunction "VCCO_35_M16") (pintype "passive"))
      (node (ref "U9") (pin "N19") (pinfunction "VCCO_34_N19") (pintype "passive"))
      (node (ref "U9") (pin "R15") (pinfunction "VCCO_34_R15") (pintype "passive"))
      (node (ref "U9") (pin "T18") (pinfunction "VCCO_34_T18") (pintype "passive"))
      (node (ref "U9") (pin "T8") (pinfunction "VCCO_13_T8") (pintype "passive"))
      (node (ref "U9") (pin "U11") (pinfunction "VCCO_13_U11") (pintype "passive"))
      (node (ref "U9") (pin "V14") (pinfunction "VCCO_34_V14") (pintype "passive"))
      (node (ref "U9") (pin "W17") (pinfunction "VCCO_34_W17") (pintype "passive"))
      (node (ref "U9") (pin "W7") (pinfunction "VCCO_13_W7") (pintype "passive"))
      (node (ref "U9") (pin "Y10") (pinfunction "VCCO_13_Y10") (pintype "passive"))
      (node (ref "U9") (pin "Y20") (pinfunction "VCCO_34_Y20") (pintype "passive"))
    )
    (net (code "6") (name "unconnected-(U9H-NC-PadT5)") (class "Default")
      (node (ref "U9") (pin "T5") (pinfunction "NC_T5") (pintype "passive"))
    )
    (net (code "7") (name "unconnected-(U9H-NC-PadT9)") (class "Default")
      (node (ref "U9") (pin "T9") (pinfunction "NC_T9") (pintype "passive"))
    )
    (net (code "8") (name "unconnected-(U9H-NC-PadU5)") (class "Default")
      (node (ref "U9") (pin "U5") (pinfunction "NC_U5") (pintype "passive"))
    )
    (net (code "9") (name "unconnected-(U9H-NC-PadU7)") (class "Default")
      (node (ref "U9") (pin "U7") (pinfunction "NC_U7") (pintype "passive"))
    )
    (net (code "10") (name "unconnected-(U9H-NC-PadU8)") (class "Default")
      (node (ref "U9") (pin "U8") (pinfunction "NC_U8") (pintype "passive"))
    )
    (net (code "11") (name "unconnected-(U9H-NC-PadU9)") (class "Default")
      (node (ref "U9") (pin "U9") (pinfunction "NC_U9") (pintype "passive"))
    )
    (net (code "12") (name "unconnected-(U9H-NC-PadU10)") (class "Default")
      (node (ref "U9") (pin "U10") (pinfunction "NC_U10") (pintype "passive"))
    )
    (net (code "13") (name "unconnected-(U9H-NC-PadV5)") (class "Default")
      (node (ref "U9") (pin "V5") (pinfunction "NC_V5") (pintype "passive"))
    )
    (net (code "14") (name "unconnected-(U9H-NC-PadV6)") (class "Default")
      (node (ref "U9") (pin "V6") (pinfunction "NC_V6") (pintype "passive"))
    )
    (net (code "15") (name "unconnected-(U9H-NC-PadV7)") (class "Default")
      (node (ref "U9") (pin "V7") (pinfunction "NC_V7") (pintype "passive"))
    )
    (net (code "16") (name "unconnected-(U9H-NC-PadV8)") (class "Default")
      (node (ref "U9") (pin "V8") (pinfunction "NC_V8") (pintype "passive"))
    )
    (net (code "17") (name "unconnected-(U9H-NC-PadV10)") (class "Default")
      (node (ref "U9") (pin "V10") (pinfunction "NC_V10") (pintype "passive"))
    )
    (net (code "18") (name "unconnected-(U9H-NC-PadV11)") (class "Default")
      (node (ref "U9") (pin "V11") (pinfunction "NC_V11") (pintype "passive"))
    )
    (net (code "19") (name "unconnected-(U9H-NC-PadW6)") (class "Default")
      (node (ref "U9") (pin "W6") (pinfunction "NC_W6") (pintype "passive"))
    )
    (net (code "20") (name "unconnected-(U9H-NC-PadW8)") (class "Default")
      (node (ref "U9") (pin "W8") (pinfunction "NC_W8") (pintype "passive"))
    )
    (net (code "21") (name "unconnected-(U9H-NC-PadW9)") (class "Default")
      (node (ref "U9") (pin "W9") (pinfunction "NC_W9") (pintype "passive"))
    )
    (net (code "22") (name "unconnected-(U9H-NC-PadW10)") (class "Default")
      (node (ref "U9") (pin "W10") (pinfunction "NC_W10") (pintype "passive"))
    )
    (net (code "23") (name "unconnected-(U9H-NC-PadW11)") (class "Default")
      (node (ref "U9") (pin "W11") (pinfunction "NC_W11") (pintype "passive"))
    )
    (net (code "24") (name "unconnected-(U9H-NC-PadY6)") (class "Default")
      (node (ref "U9") (pin "Y6") (pinfunction "NC_Y6") (pintype "passive"))
    )
    (net (code "25") (name "unconnected-(U9H-NC-PadY7)") (class "Default")
      (node (ref "U9") (pin "Y7") (pinfunction "NC_Y7") (pintype "passive"))
    )
    (net (code "26") (name "unconnected-(U9H-NC-PadY8)") (class "Default")
      (node (ref "U9") (pin "Y8") (pinfunction "NC_Y8") (pintype "passive"))
    )
    (net (code "27") (name "unconnected-(U9H-NC-PadY9)") (class "Default")
      (node (ref "U9") (pin "Y9") (pinfunction "NC_Y9") (pintype "passive"))
    )
    (net (code "28") (name "unconnected-(U9H-NC-PadY11)") (class "Default")
      (node (ref "U9") (pin "Y11") (pinfunction "NC_Y11") (pintype "passive"))
    )
    (net (code "29") (name "unconnected-(U9H-NC-PadY12)") (class "Default")
      (node (ref "U9") (pin "Y12") (pinfunction "NC_Y12") (pintype "passive"))
    )
    (net (code "30") (name "unconnected-(U9H-NC-PadY13)") (class "Default")
      (node (ref "U9") (pin "Y13") (pinfunction "NC_Y13") (pintype "passive"))
    )
  )
)
